# Temp_Sensor_C.net
KiCad netlist of a schematic drawn in EAGLE
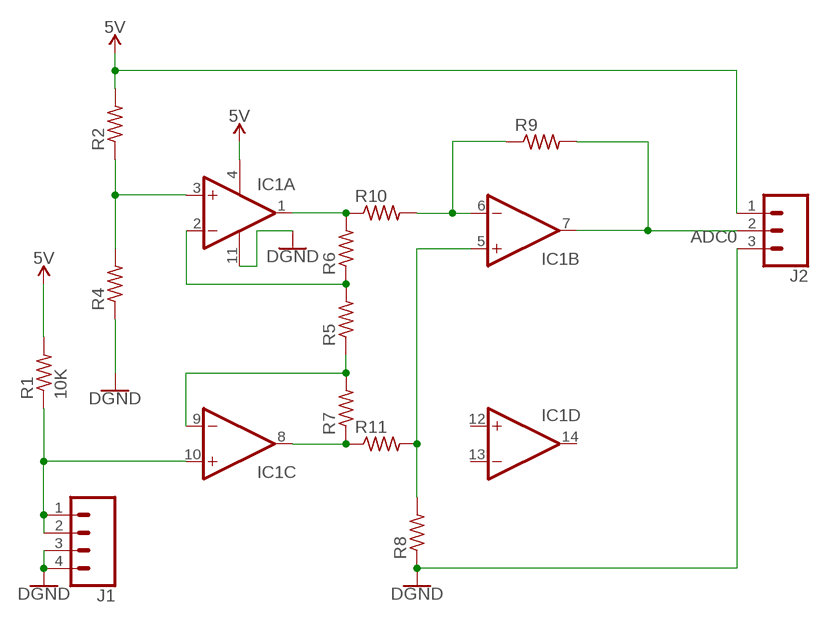
[diagram p0: schematic, sheet 1]

(export (version "E")
  (design (tool "Eeschema 10.0.6"))
  (components
    (comp (ref "IC1")
      (value "MCP604SL")
      (footprint "eagle-import:SO14")
      (libsource (lib "eagle-import") (part "MCP604SL"))
    )
    (comp (ref "J1")
      (value "CONN_04SCREW")
      (footprint "eagle-import:SCREWTERMINAL-3.5MM-4")
      (libsource (lib "eagle-import") (part "CONN_04SCREW"))
    )
    (comp (ref "J2")
      (value "455-1750-1-ND")
      (footprint "eagle-import:1X03")
      (libsource (lib "eagle-import") (part "CONN_03"))
    )
    (comp (ref "R1")
      (value "10K")
      (footprint "eagle-import:R0603")
      (libsource (lib "eagle-import") (part "R-US_R0603"))
    )
    (comp (ref "R2")
      (value "R-US_R0603")
      (footprint "eagle-import:R0603")
      (libsource (lib "eagle-import") (part "R-US_R0603"))
    )
    (comp (ref "R4")
      (value "R-US_R0603")
      (footprint "eagle-import:R0603")
      (libsource (lib "eagle-import") (part "R-US_R0603"))
    )
    (comp (ref "R5")
      (value "R-US_R0603")
      (footprint "eagle-import:R0603")
      (libsource (lib "eagle-import") (part "R-US_R0603"))
    )
    (comp (ref "R6")
      (value "R-US_R0603")
      (footprint "eagle-import:R0603")
      (libsource (lib "eagle-import") (part "R-US_R0603"))
    )
    (comp (ref "R7")
      (value "R-US_R0603")
      (footprint "eagle-import:R0603")
      (libsource (lib "eagle-import") (part "R-US_R0603"))
    )
    (comp (ref "R8")
      (value "R-US_R0603")
      (footprint "eagle-import:R0603")
      (libsource (lib "eagle-import") (part "R-US_R0603"))
    )
    (comp (ref "R9")
      (value "R-US_R0603")
      (footprint "eagle-import:R0603")
      (libsource (lib "eagle-import") (part "R-US_R0603"))
    )
    (comp (ref "R10")
      (value "R-US_R0603")
      (footprint "eagle-import:R0603")
      (libsource (lib "eagle-import") (part "R-US_R0603"))
    )
    (comp (ref "R11")
      (value "R-US_R0603")
      (footprint "eagle-import:R0603")
      (libsource (lib "eagle-import") (part "R-US_R0603"))
    )
  )
  (nets
    (net (code "1") (name "/ADC0") (class "Default")
      (node (ref "IC1") (pin "7") (pinfunction "OUT_7") (pintype "output"))
      (node (ref "J2") (pin "2") (pinfunction "2_2") (pintype "passive"))
      (node (ref "R9") (pin "2") (pinfunction "2_2") (pintype "passive"))
    )
    (net (code "2") (name "5V") (class "Default")
      (node (ref "IC1") (pin "4") (pinfunction "V+_4") (pintype "power_in"))
      (node (ref "J2") (pin "1") (pinfunction "1_1") (pintype "passive"))
      (node (ref "R1") (pin "2") (pinfunction "2_2") (pintype "passive"))
      (node (ref "R2") (pin "2") (pinfunction "2_2") (pintype "passive"))
    )
    (net (code "3") (name "DGND") (class "Default")
      (node (ref "IC1") (pin "11") (pinfunction "V-_11") (pintype "power_in"))
      (node (ref "J1") (pin "3") (pinfunction "3_3") (pintype "passive"))
      (node (ref "J1") (pin "4") (pinfunction "4_4") (pintype "passive"))
      (node (ref "J2") (pin "3") (pinfunction "3_3") (pintype "passive"))
      (node (ref "R4") (pin "1") (pinfunction "1_1") (pintype "passive"))
      (node (ref "R8") (pin "1") (pinfunction "1_1") (pintype "passive"))
    )
    (net (code "4") (name "Net-(IC1A-+IN)") (class "Default")
      (node (ref "IC1") (pin "3") (pinfunction "+IN_3") (pintype "input"))
      (node (ref "R2") (pin "1") (pinfunction "1_1") (pintype "passive"))
      (node (ref "R4") (pin "2") (pinfunction "2_2") (pintype "passive"))
    )
    (net (code "5") (name "Net-(IC1A--IN)") (class "Default")
      (node (ref "IC1") (pin "2") (pinfunction "-IN_2") (pintype "input"))
      (node (ref "R5") (pin "2") (pinfunction "2_2") (pintype "passive"))
      (node (ref "R6") (pin "1") (pinfunction "1_1") (pintype "passive"))
    )
    (net (code "6") (name "Net-(IC1A-OUT)") (class "Default")
      (node (ref "IC1") (pin "1") (pinfunction "OUT_1") (pintype "output"))
      (node (ref "R10") (pin "1") (pinfunction "1_1") (pintype "passive"))
      (node (ref "R6") (pin "2") (pinfunction "2_2") (pintype "passive"))
    )
    (net (code "7") (name "Net-(IC1B-+IN)") (class "Default")
      (node (ref "IC1") (pin "5") (pinfunction "+IN_5") (pintype "input"))
      (node (ref "R11") (pin "2") (pinfunction "2_2") (pintype "passive"))
      (node (ref "R8") (pin "2") (pinfunction "2_2") (pintype "passive"))
    )
    (net (code "8") (name "Net-(IC1B--IN)") (class "Default")
      (node (ref "IC1") (pin "6") (pinfunction "-IN_6") (pintype "input"))
      (node (ref "R10") (pin "2") (pinfunction "2_2") (pintype "passive"))
      (node (ref "R9") (pin "1") (pinfunction "1_1") (pintype "passive"))
    )
    (net (code "9") (name "Net-(IC1C-+IN)") (class "Default")
      (node (ref "IC1") (pin "10") (pinfunction "+IN_10") (pintype "input"))
      (node (ref "J1") (pin "1") (pinfunction "1_1") (pintype "passive"))
      (node (ref "J1") (pin "2") (pinfunction "2_2") (pintype "passive"))
      (node (ref "R1") (pin "1") (pinfunction "1_1") (pintype "passive"))
    )
    (net (code "10") (name "Net-(IC1C--IN)") (class "Default")
      (node (ref "IC1") (pin "9") (pinfunction "-IN_9") (pintype "input"))
      (node (ref "R5") (pin "1") (pinfunction "1_1") (pintype "passive"))
      (node (ref "R7") (pin "2") (pinfunction "2_2") (pintype "passive"))
    )
    (net (code "11") (name "Net-(IC1C-OUT)") (class "Default")
      (node (ref "IC1") (pin "8") (pinfunction "OUT_8") (pintype "output"))
      (node (ref "R11") (pin "1") (pinfunction "1_1") (pintype "passive"))
      (node (ref "R7") (pin "1") (pinfunction "1_1") (pintype "passive"))
    )
    (net (code "12") (name "unconnected-(IC1D-+IN-Pad12)") (class "Default")
      (node (ref "IC1") (pin "12") (pinfunction "+IN_12") (pintype "input"))
    )
    (net (code "13") (name "unconnected-(IC1D--IN-Pad13)") (class "Default")
      (node (ref "IC1") (pin "13") (pinfunction "-IN_13") (pintype "input"))
    )
    (net (code "14") (name "unconnected-(IC1D-OUT-Pad14)") (class "Default")
      (node (ref "IC1") (pin "14") (pinfunction "OUT_14") (pintype "output"))
    )
  )
)
